# design.net
KiCad netlist of a schematic drawn in Altium Designer
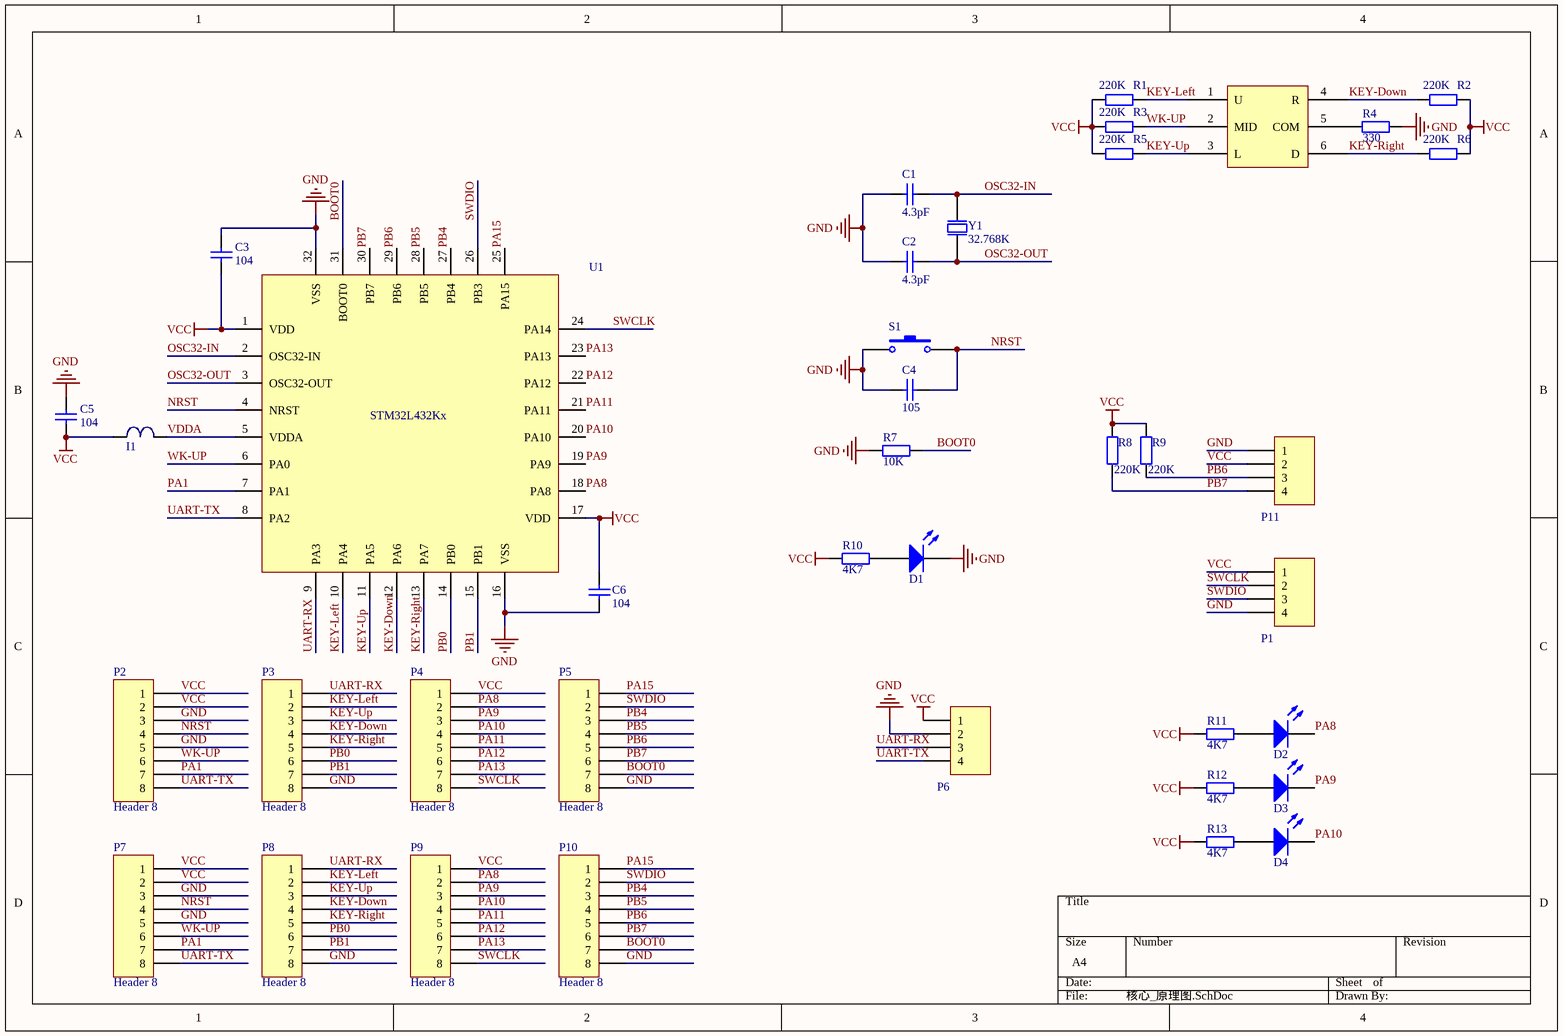
[diagram p0: 核心_原理图.SchDoc]

(export (version "E")
  (design (tool "Eeschema 10.0.6"))
  (components
    (comp (ref "C1")
      (value "4.3pF")
      (footprint "1__0603-CAP_")
      (description "Capacitor")
      (libsource (lib "Miscellaneous Devices") (part "Cap"))
    )
    (comp (ref "C2")
      (value "4.3pF")
      (footprint "1__0603-CAP_")
      (description "Capacitor")
      (libsource (lib "Miscellaneous Devices") (part "Cap"))
    )
    (comp (ref "C3")
      (value "104")
      (footprint "1__0603-CAP_")
      (description "Capacitor")
      (libsource (lib "Miscellaneous Devices") (part "Cap"))
    )
    (comp (ref "C4")
      (value "105")
      (footprint "1__0603-CAP_")
      (description "Capacitor")
      (libsource (lib "Miscellaneous Devices") (part "Cap"))
    )
    (comp (ref "C5")
      (value "104")
      (footprint "1__0603-CAP_")
      (description "Capacitor")
      (libsource (lib "Miscellaneous Devices") (part "Cap"))
    )
    (comp (ref "C6")
      (value "104")
      (footprint "1__0603-CAP_")
      (description "Capacitor")
      (libsource (lib "Miscellaneous Devices") (part "Cap"))
    )
    (comp (ref "D1")
      (value "LED")
      (footprint "1__0603-LED_")
      (description "Typical INFRARED GaAs LED")
      (libsource (lib "Miscellaneous Devices") (part "LED0"))
    )
    (comp (ref "D2")
      (value "LED")
      (footprint "1__0603-LED_")
      (description "Typical INFRARED GaAs LED")
      (libsource (lib "Miscellaneous Devices") (part "LED0"))
    )
    (comp (ref "D3")
      (value "LED")
      (footprint "1__0603-LED_")
      (description "Typical INFRARED GaAs LED")
      (libsource (lib "Miscellaneous Devices") (part "LED0"))
    )
    (comp (ref "D4")
      (value "LED")
      (footprint "1__0603-LED_")
      (description "Typical INFRARED GaAs LED")
      (libsource (lib "Miscellaneous Devices") (part "LED0"))
    )
    (comp (ref "I1") (value "100uH") (footprint "1__0603_Ind_") (libsource (lib "常用原理图_by_K") (part "电感")))
    (comp (ref "P1")
      (value "~")
      (footprint "HDR1X4")
      (description "Header, 4-Pin")
      (libsource (lib "!)Miscellaneous Integrated Library") (part "Header 4"))
    )
    (comp (ref "P2")
      (value "Header 8")
      (footprint "HDR1X8")
      (description "Header, 8-Pin")
      (fields (field (name "PUBLISHER") "Altium Limited"))
      (libsource (lib "!)Miscellaneous Integrated Library") (part "Header 8"))
    )
    (comp (ref "P3")
      (value "Header 8")
      (footprint "HDR1X8")
      (description "Header, 8-Pin")
      (fields (field (name "PUBLISHER") "Altium Limited"))
      (libsource (lib "!)Miscellaneous Integrated Library") (part "Header 8"))
    )
    (comp (ref "P4")
      (value "Header 8")
      (footprint "HDR1X8")
      (description "Header, 8-Pin")
      (fields (field (name "PUBLISHER") "Altium Limited"))
      (libsource (lib "!)Miscellaneous Integrated Library") (part "Header 8"))
    )
    (comp (ref "P5")
      (value "Header 8")
      (footprint "HDR1X8")
      (description "Header, 8-Pin")
      (fields (field (name "PUBLISHER") "Altium Limited"))
      (libsource (lib "!)Miscellaneous Integrated Library") (part "Header 8"))
    )
    (comp (ref "P6")
      (value "蓝牙")
      (footprint "HDR1X4")
      (description "Header, 4-Pin")
      (libsource (lib "!)Miscellaneous Integrated Library") (part "Header 4"))
    )
    (comp (ref "P7")
      (value "Header 8")
      (footprint "HDR1X8")
      (description "Header, 8-Pin")
      (fields (field (name "PUBLISHER") "Altium Limited"))
      (libsource (lib "!)Miscellaneous Integrated Library") (part "Header 8"))
    )
    (comp (ref "P8")
      (value "Header 8")
      (footprint "HDR1X8")
      (description "Header, 8-Pin")
      (fields (field (name "PUBLISHER") "Altium Limited"))
      (libsource (lib "!)Miscellaneous Integrated Library") (part "Header 8"))
    )
    (comp (ref "P9")
      (value "Header 8")
      (footprint "HDR1X8")
      (description "Header, 8-Pin")
      (fields (field (name "PUBLISHER") "Altium Limited"))
      (libsource (lib "!)Miscellaneous Integrated Library") (part "Header 8"))
    )
    (comp (ref "P10")
      (value "Header 8")
      (footprint "HDR1X8")
      (description "Header, 8-Pin")
      (fields (field (name "PUBLISHER") "Altium Limited"))
      (libsource (lib "!)Miscellaneous Integrated Library") (part "Header 8"))
    )
    (comp (ref "P11")
      (value "~")
      (footprint "HDR1X4")
      (description "Header, 4-Pin")
      (libsource (lib "!)Miscellaneous Integrated Library") (part "Header 4"))
    )
    (comp (ref "R1")
      (value "220K")
      (footprint "1__0603-RES_")
      (description "Resistor")
      (libsource (lib "Miscellaneous Devices") (part "Res2"))
    )
    (comp (ref "R2")
      (value "220K")
      (footprint "1__0603-RES_")
      (description "Resistor")
      (libsource (lib "Miscellaneous Devices") (part "Res2"))
    )
    (comp (ref "R3")
      (value "220K")
      (footprint "1__0603-RES_")
      (description "Resistor")
      (libsource (lib "Miscellaneous Devices") (part "Res2"))
    )
    (comp (ref "R4")
      (value "330")
      (footprint "1__0603-RES_")
      (description "Resistor")
      (libsource (lib "") (part "Res2_2"))
    )
    (comp (ref "R5")
      (value "220K")
      (footprint "1__0603-RES_")
      (description "Resistor")
      (libsource (lib "Miscellaneous Devices") (part "Res2"))
    )
    (comp (ref "R6")
      (value "220K")
      (footprint "1__0603-RES_")
      (description "Resistor")
      (libsource (lib "Miscellaneous Devices") (part "Res2"))
    )
    (comp (ref "R7")
      (value "10K")
      (footprint "1__0603-RES_")
      (description "Resistor")
      (libsource (lib "") (part "Res2_2"))
    )
    (comp (ref "R8")
      (value "220K")
      (footprint "1__0603-RES_")
      (description "Resistor")
      (libsource (lib "") (part "Res2_1"))
    )
    (comp (ref "R9")
      (value "220K")
      (footprint "1__0603-RES_")
      (description "Resistor")
      (libsource (lib "") (part "Res2_1"))
    )
    (comp (ref "R10")
      (value "4K7")
      (footprint "1__0603-RES_")
      (description "Resistor")
      (libsource (lib "") (part "Res2_1"))
    )
    (comp (ref "R11")
      (value "4K7")
      (footprint "1__0603-RES_")
      (description "Resistor")
      (libsource (lib "") (part "Res2_1"))
    )
    (comp (ref "R12")
      (value "4K7")
      (footprint "1__0603-RES_")
      (description "Resistor")
      (libsource (lib "") (part "Res2_1"))
    )
    (comp (ref "R13")
      (value "4K7")
      (footprint "1__0603-RES_")
      (description "Resistor")
      (libsource (lib "") (part "Res2_1"))
    )
    (comp (ref "S1")
      (value "~")
      (footprint "key3*4*2")
      (description "Switch")
      (libsource (lib "Miscellaneous Devices") (part "SW-PB"))
    )
    (comp (ref "U1")
      (value "STM32L432Kx")
      (footprint "STM32L432")
      (description "单片机")
      (libsource (lib "原理图库") (part "STM32L432Kx"))
    )
    (comp (ref "Y1")
      (value "32.768K")
      (footprint "OSC32")
      (description "Crystal Oscillator")
      (libsource (lib "!)Miscellaneous Integrated Library") (part "XTAL"))
    )
    (comp (ref "五向按键1") (value "五向按键") (footprint "1__五向按键_") (libsource (lib "没有的器件原理图") (part "五向按键")))
  )
  (nets
    (net (code "2") (name "/BOOT0") (class "Default")
      (node (ref "P10") (pin "7") (pinfunction "7_7") (pintype "passive"))
      (node (ref "P5") (pin "7") (pinfunction "7_7") (pintype "passive"))
      (node (ref "R7") (pin "1") (pinfunction "1_1") (pintype "passive"))
      (node (ref "U1") (pin "31") (pinfunction "BOOT0_31") (pintype "passive"))
    )
    (net (code "3") (name "/KEY-Down") (class "Default")
      (node (ref "P3") (pin "4") (pinfunction "4_4") (pintype "passive"))
      (node (ref "P8") (pin "4") (pinfunction "4_4") (pintype "passive"))
      (node (ref "R2") (pin "1") (pinfunction "1_1") (pintype "passive"))
      (node (ref "U1") (pin "12") (pinfunction "PA6_12") (pintype "passive"))
      (node (ref "五向按键1") (pin "4") (pinfunction "R_4") (pintype "passive"))
    )
    (net (code "4") (name "/KEY-Left") (class "Default")
      (node (ref "P3") (pin "2") (pinfunction "2_2") (pintype "passive"))
      (node (ref "P8") (pin "2") (pinfunction "2_2") (pintype "passive"))
      (node (ref "R1") (pin "2") (pinfunction "2_2") (pintype "passive"))
      (node (ref "U1") (pin "10") (pinfunction "PA4_10") (pintype "passive"))
      (node (ref "五向按键1") (pin "1") (pinfunction "U_1") (pintype "passive"))
    )
    (net (code "5") (name "/KEY-Right") (class "Default")
      (node (ref "P3") (pin "5") (pinfunction "5_5") (pintype "passive"))
      (node (ref "P8") (pin "5") (pinfunction "5_5") (pintype "passive"))
      (node (ref "R6") (pin "1") (pinfunction "1_1") (pintype "passive"))
      (node (ref "U1") (pin "13") (pinfunction "PA7_13") (pintype "passive"))
      (node (ref "五向按键1") (pin "6") (pinfunction "D_6") (pintype "passive"))
    )
    (net (code "6") (name "/KEY-Up") (class "Default")
      (node (ref "P3") (pin "3") (pinfunction "3_3") (pintype "passive"))
      (node (ref "P8") (pin "3") (pinfunction "3_3") (pintype "passive"))
      (node (ref "R5") (pin "2") (pinfunction "2_2") (pintype "passive"))
      (node (ref "U1") (pin "11") (pinfunction "PA5_11") (pintype "passive"))
      (node (ref "五向按键1") (pin "3") (pinfunction "L_3") (pintype "passive"))
    )
    (net (code "7") (name "/NRST") (class "Default")
      (node (ref "C4") (pin "2") (pinfunction "2_2") (pintype "passive"))
      (node (ref "P2") (pin "4") (pinfunction "4_4") (pintype "passive"))
      (node (ref "P7") (pin "4") (pinfunction "4_4") (pintype "passive"))
      (node (ref "S1") (pin "2") (pinfunction "2_2") (pintype "passive"))
      (node (ref "U1") (pin "4") (pinfunction "NRST_4") (pintype "passive"))
    )
    (net (code "8") (name "/OSC32-IN") (class "Default")
      (node (ref "C1") (pin "1") (pinfunction "1_1") (pintype "passive"))
      (node (ref "U1") (pin "2") (pinfunction "OSC32-IN_2") (pintype "passive"))
      (node (ref "Y1") (pin "2") (pinfunction "OSC2_2") (pintype "passive"))
    )
    (net (code "9") (name "/OSC32-OUT") (class "Default")
      (node (ref "C2") (pin "1") (pinfunction "1_1") (pintype "passive"))
      (node (ref "U1") (pin "3") (pinfunction "OSC32-OUT_3") (pintype "passive"))
      (node (ref "Y1") (pin "1") (pinfunction "OSC1_1") (pintype "passive"))
    )
    (net (code "10") (name "/PA1") (class "Default")
      (node (ref "P2") (pin "7") (pinfunction "7_7") (pintype "passive"))
      (node (ref "P7") (pin "7") (pinfunction "7_7") (pintype "passive"))
      (node (ref "U1") (pin "7") (pinfunction "PA1_7") (pintype "passive"))
    )
    (net (code "11") (name "/PA8") (class "Default")
      (node (ref "D2") (pin "2") (pinfunction "2_2") (pintype "passive"))
      (node (ref "P4") (pin "2") (pinfunction "2_2") (pintype "passive"))
      (node (ref "P9") (pin "2") (pinfunction "2_2") (pintype "passive"))
      (node (ref "U1") (pin "18") (pinfunction "PA8_18") (pintype "passive"))
    )
    (net (code "12") (name "/PA9") (class "Default")
      (node (ref "D3") (pin "2") (pinfunction "2_2") (pintype "passive"))
      (node (ref "P4") (pin "3") (pinfunction "3_3") (pintype "passive"))
      (node (ref "P9") (pin "3") (pinfunction "3_3") (pintype "passive"))
      (node (ref "U1") (pin "19") (pinfunction "PA9_19") (pintype "passive"))
    )
    (net (code "13") (name "/PA10") (class "Default")
      (node (ref "D4") (pin "2") (pinfunction "2_2") (pintype "passive"))
      (node (ref "P4") (pin "4") (pinfunction "4_4") (pintype "passive"))
      (node (ref "P9") (pin "4") (pinfunction "4_4") (pintype "passive"))
      (node (ref "U1") (pin "20") (pinfunction "PA10_20") (pintype "passive"))
    )
    (net (code "14") (name "/PA11") (class "Default")
      (node (ref "P4") (pin "5") (pinfunction "5_5") (pintype "passive"))
      (node (ref "P9") (pin "5") (pinfunction "5_5") (pintype "passive"))
      (node (ref "U1") (pin "21") (pinfunction "PA11_21") (pintype "passive"))
    )
    (net (code "15") (name "/PA12") (class "Default")
      (node (ref "P4") (pin "6") (pinfunction "6_6") (pintype "passive"))
      (node (ref "P9") (pin "6") (pinfunction "6_6") (pintype "passive"))
      (node (ref "U1") (pin "22") (pinfunction "PA12_22") (pintype "passive"))
    )
    (net (code "16") (name "/PA13") (class "Default")
      (node (ref "P4") (pin "7") (pinfunction "7_7") (pintype "passive"))
      (node (ref "P9") (pin "7") (pinfunction "7_7") (pintype "passive"))
      (node (ref "U1") (pin "23") (pinfunction "PA13_23") (pintype "passive"))
    )
    (net (code "17") (name "/PA15") (class "Default")
      (node (ref "P10") (pin "1") (pinfunction "1_1") (pintype "passive"))
      (node (ref "P5") (pin "1") (pinfunction "1_1") (pintype "passive"))
      (node (ref "U1") (pin "25") (pinfunction "PA15_25") (pintype "passive"))
    )
    (net (code "18") (name "/PB0") (class "Default")
      (node (ref "P3") (pin "6") (pinfunction "6_6") (pintype "passive"))
      (node (ref "P8") (pin "6") (pinfunction "6_6") (pintype "passive"))
      (node (ref "U1") (pin "14") (pinfunction "PB0_14") (pintype "passive"))
    )
    (net (code "19") (name "/PB1") (class "Default")
      (node (ref "P3") (pin "7") (pinfunction "7_7") (pintype "passive"))
      (node (ref "P8") (pin "7") (pinfunction "7_7") (pintype "passive"))
      (node (ref "U1") (pin "15") (pinfunction "PB1_15") (pintype "passive"))
    )
    (net (code "20") (name "/PB4") (class "Default")
      (node (ref "P10") (pin "3") (pinfunction "3_3") (pintype "passive"))
      (node (ref "P5") (pin "3") (pinfunction "3_3") (pintype "passive"))
      (node (ref "U1") (pin "27") (pinfunction "PB4_27") (pintype "passive"))
    )
    (net (code "21") (name "/PB5") (class "Default")
      (node (ref "P10") (pin "4") (pinfunction "4_4") (pintype "passive"))
      (node (ref "P5") (pin "4") (pinfunction "4_4") (pintype "passive"))
      (node (ref "U1") (pin "28") (pinfunction "PB5_28") (pintype "passive"))
    )
    (net (code "22") (name "/PB6") (class "Default")
      (node (ref "P10") (pin "5") (pinfunction "5_5") (pintype "passive"))
      (node (ref "P11") (pin "3") (pinfunction "3_3") (pintype "passive"))
      (node (ref "P5") (pin "5") (pinfunction "5_5") (pintype "passive"))
      (node (ref "R9") (pin "1") (pinfunction "1_1") (pintype "passive"))
      (node (ref "U1") (pin "29") (pinfunction "PB6_29") (pintype "passive"))
    )
    (net (code "23") (name "/PB7") (class "Default")
      (node (ref "P10") (pin "6") (pinfunction "6_6") (pintype "passive"))
      (node (ref "P11") (pin "4") (pinfunction "4_4") (pintype "passive"))
      (node (ref "P5") (pin "6") (pinfunction "6_6") (pintype "passive"))
      (node (ref "R8") (pin "1") (pinfunction "1_1") (pintype "passive"))
      (node (ref "U1") (pin "30") (pinfunction "PB7_30") (pintype "passive"))
    )
    (net (code "24") (name "/SWCLK") (class "Default")
      (node (ref "P1") (pin "2") (pinfunction "2_2") (pintype "passive"))
      (node (ref "P4") (pin "8") (pinfunction "8_8") (pintype "passive"))
      (node (ref "P9") (pin "8") (pinfunction "8_8") (pintype "passive"))
      (node (ref "U1") (pin "24") (pinfunction "PA14_24") (pintype "passive"))
    )
    (net (code "25") (name "/SWDIO") (class "Default")
      (node (ref "P1") (pin "3") (pinfunction "3_3") (pintype "passive"))
      (node (ref "P10") (pin "2") (pinfunction "2_2") (pintype "passive"))
      (node (ref "P5") (pin "2") (pinfunction "2_2") (pintype "passive"))
      (node (ref "U1") (pin "26") (pinfunction "PB3_26") (pintype "passive"))
    )
    (net (code "26") (name "/UART-RX") (class "Default")
      (node (ref "P3") (pin "1") (pinfunction "1_1") (pintype "passive"))
      (node (ref "P6") (pin "3") (pinfunction "3_3") (pintype "passive"))
      (node (ref "P8") (pin "1") (pinfunction "1_1") (pintype "passive"))
      (node (ref "U1") (pin "9") (pinfunction "PA3_9") (pintype "passive"))
    )
    (net (code "27") (name "/UART-TX") (class "Default")
      (node (ref "P2") (pin "8") (pinfunction "8_8") (pintype "passive"))
      (node (ref "P6") (pin "4") (pinfunction "4_4") (pintype "passive"))
      (node (ref "P7") (pin "8") (pinfunction "8_8") (pintype "passive"))
      (node (ref "U1") (pin "8") (pinfunction "PA2_8") (pintype "passive"))
    )
    (net (code "28") (name "/VDDA") (class "Default")
      (node (ref "I1") (pin "2") (pinfunction "2_2") (pintype "passive"))
      (node (ref "U1") (pin "5") (pinfunction "VDDA_5") (pintype "passive"))
    )
    (net (code "29") (name "/WK-UP") (class "Default")
      (node (ref "P2") (pin "6") (pinfunction "6_6") (pintype "passive"))
      (node (ref "P7") (pin "6") (pinfunction "6_6") (pintype "passive"))
      (node (ref "R3") (pin "2") (pinfunction "2_2") (pintype "passive"))
      (node (ref "U1") (pin "6") (pinfunction "PA0_6") (pintype "passive"))
      (node (ref "五向按键1") (pin "2") (pinfunction "MID_2") (pintype "passive"))
    )
    (net (code "30") (name "GND") (class "Default")
      (node (ref "C1") (pin "2") (pinfunction "2_2") (pintype "passive"))
      (node (ref "C2") (pin "2") (pinfunction "2_2") (pintype "passive"))
      (node (ref "C3") (pin "2") (pinfunction "2_2") (pintype "passive"))
      (node (ref "C4") (pin "1") (pinfunction "1_1") (pintype "passive"))
      (node (ref "C5") (pin "2") (pinfunction "2_2") (pintype "passive"))
      (node (ref "C6") (pin "2") (pinfunction "2_2") (pintype "passive"))
      (node (ref "D1") (pin "2") (pinfunction "2_2") (pintype "passive"))
      (node (ref "P1") (pin "4") (pinfunction "4_4") (pintype "passive"))
      (node (ref "P10") (pin "8") (pinfunction "8_8") (pintype "passive"))
      (node (ref "P11") (pin "1") (pinfunction "1_1") (pintype "passive"))
      (node (ref "P2") (pin "3") (pinfunction "3_3") (pintype "passive"))
      (node (ref "P2") (pin "5") (pinfunction "5_5") (pintype "passive"))
      (node (ref "P3") (pin "8") (pinfunction "8_8") (pintype "passive"))
      (node (ref "P5") (pin "8") (pinfunction "8_8") (pintype "passive"))
      (node (ref "P6") (pin "2") (pinfunction "2_2") (pintype "passive"))
      (node (ref "P7") (pin "3") (pinfunction "3_3") (pintype "passive"))
      (node (ref "P7") (pin "5") (pinfunction "5_5") (pintype "passive"))
      (node (ref "P8") (pin "8") (pinfunction "8_8") (pintype "passive"))
      (node (ref "R4") (pin "1") (pinfunction "1_1") (pintype "passive"))
      (node (ref "R7") (pin "2") (pinfunction "2_2") (pintype "passive"))
      (node (ref "S1") (pin "1") (pinfunction "1_1") (pintype "passive"))
      (node (ref "U1") (pin "16") (pinfunction "VSS_16") (pintype "passive"))
      (node (ref "U1") (pin "32") (pinfunction "VSS_32") (pintype "passive"))
    )
    (net (code "31") (name "Net-(D1-Pad1)") (class "Default")
      (node (ref "D1") (pin "1") (pinfunction "1_1") (pintype "passive"))
      (node (ref "R10") (pin "2") (pinfunction "2_2") (pintype "passive"))
    )
    (net (code "32") (name "Net-(D2-Pad1)") (class "Default")
      (node (ref "D2") (pin "1") (pinfunction "1_1") (pintype "passive"))
      (node (ref "R11") (pin "2") (pinfunction "2_2") (pintype "passive"))
    )
    (net (code "33") (name "Net-(D3-Pad1)") (class "Default")
      (node (ref "D3") (pin "1") (pinfunction "1_1") (pintype "passive"))
      (node (ref "R12") (pin "2") (pinfunction "2_2") (pintype "passive"))
    )
    (net (code "34") (name "Net-(D4-Pad1)") (class "Default")
      (node (ref "D4") (pin "1") (pinfunction "1_1") (pintype "passive"))
      (node (ref "R13") (pin "2") (pinfunction "2_2") (pintype "passive"))
    )
    (net (code "35") (name "Net-(五向按键1-COM)") (class "Default")
      (node (ref "R4") (pin "2") (pinfunction "2_2") (pintype "passive"))
      (node (ref "五向按键1") (pin "5") (pinfunction "COM_5") (pintype "passive"))
    )
    (net (code "36") (name "VCC") (class "Default")
      (node (ref "C3") (pin "1") (pinfunction "1_1") (pintype "passive"))
      (node (ref "C5") (pin "1") (pinfunction "1_1") (pintype "passive"))
      (node (ref "C6") (pin "1") (pinfunction "1_1") (pintype "passive"))
      (node (ref "I1") (pin "1") (pinfunction "1_1") (pintype "passive"))
      (node (ref "P1") (pin "1") (pinfunction "1_1") (pintype "passive"))
      (node (ref "P11") (pin "2") (pinfunction "2_2") (pintype "passive"))
      (node (ref "P2") (pin "1") (pinfunction "1_1") (pintype "passive"))
      (node (ref "P2") (pin "2") (pinfunction "2_2") (pintype "passive"))
      (node (ref "P4") (pin "1") (pinfunction "1_1") (pintype "passive"))
      (node (ref "P6") (pin "1") (pinfunction "1_1") (pintype "passive"))
      (node (ref "P7") (pin "1") (pinfunction "1_1") (pintype "passive"))
      (node (ref "P7") (pin "2") (pinfunction "2_2") (pintype "passive"))
      (node (ref "P9") (pin "1") (pinfunction "1_1") (pintype "passive"))
      (node (ref "R1") (pin "1") (pinfunction "1_1") (pintype "passive"))
      (node (ref "R10") (pin "1") (pinfunction "1_1") (pintype "passive"))
      (node (ref "R11") (pin "1") (pinfunction "1_1") (pintype "passive"))
      (node (ref "R12") (pin "1") (pinfunction "1_1") (pintype "passive"))
      (node (ref "R13") (pin "1") (pinfunction "1_1") (pintype "passive"))
      (node (ref "R2") (pin "2") (pinfunction "2_2") (pintype "passive"))
      (node (ref "R3") (pin "1") (pinfunction "1_1") (pintype "passive"))
      (node (ref "R5") (pin "1") (pinfunction "1_1") (pintype "passive"))
      (node (ref "R6") (pin "2") (pinfunction "2_2") (pintype "passive"))
      (node (ref "R8") (pin "2") (pinfunction "2_2") (pintype "passive"))
      (node (ref "R9") (pin "2") (pinfunction "2_2") (pintype "passive"))
      (node (ref "U1") (pin "1") (pinfunction "VDD_1") (pintype "passive"))
      (node (ref "U1") (pin "17") (pinfunction "VDD_17") (pintype "passive"))
    )
  )
)
